# HUMI.net
KiCad netlist of a schematic drawn in Altium Designer
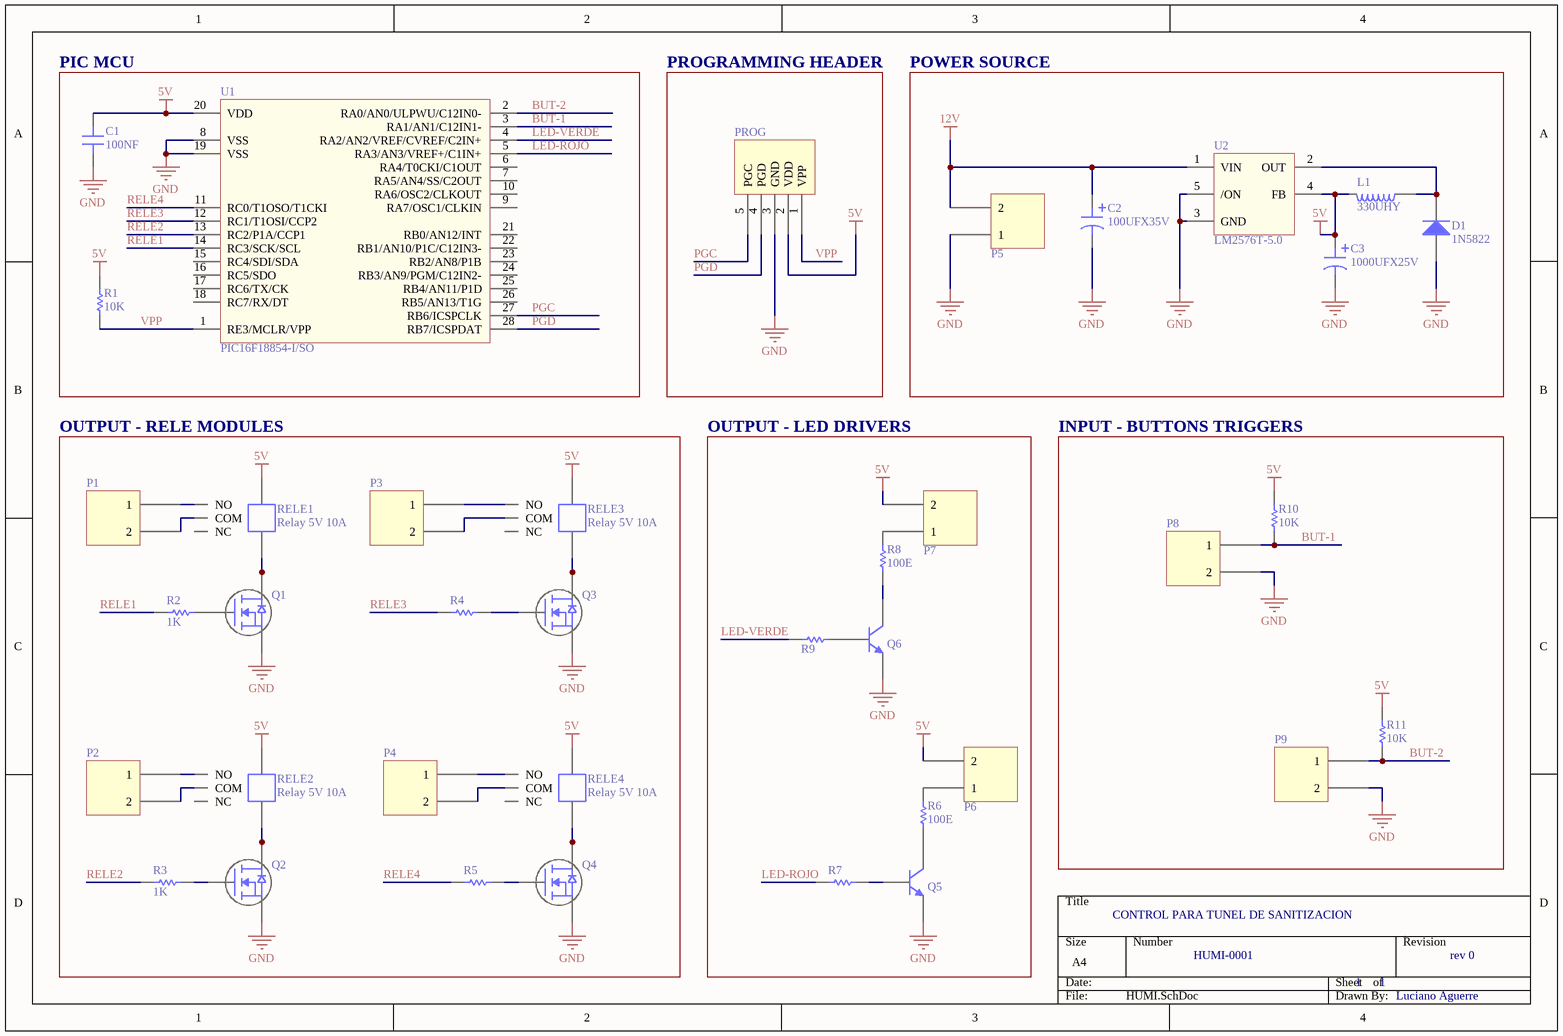
[diagram p0: HUMI.SchDoc]

(export (version "E")
  (design (tool "Eeschema 10.0.6"))
  (components
    (comp (ref "C1")
      (value "100NF")
      (footprint "CAP.SMD.0805")
      (description "100NFX50V X7R 10% CER.MULT. SMD 0805")
      (libsource (lib "Libreria-Capacitores") (part "Capacitor 100NFX50V X7R 10% CER.MULT. SMD 0805"))
    )
    (comp (ref "C2")
      (value "100UFX35V")
      (footprint "CAP-ELEC-8X11")
      (description "100UFX35V 85°C 8x11 ELE.RAD AISHI")
      (libsource (lib "Libreria-Capacitores") (part "Capacitor Electrolitico 100UFX35V 85°C 8x11 ELE.RAD AISHI"))
    )
    (comp (ref "C3")
      (value "1000UFX25V")
      (footprint "CAP-ELEC-12.5X20")
      (description "1000UFX25V 85°C 12.5X20 ELE.RAD AISHI")
      (libsource (lib "Libreria-Capacitores") (part "Capacitor Electrolitico 1000UFX25V 85°C 12.5X20 ELE.RAD AISHI"))
    )
    (comp (ref "D1")
      (value "1N5822")
      (footprint "Diode 1N5822")
      (description "Diodo Schottky 1N5822 3A 40V")
      (libsource (lib "Libreria-Diodos") (part "Diodo Schottky 1N5822 3A 40V"))
    )
    (comp (ref "L1")
      (value "330UHY")
      (footprint "Inductor Radial DR1213")
      (description "330UHY 0.3R 1.4A RAD. 15.5X15.5MM")
      (libsource (lib "Libreria-Inductores") (part "Inductor Radial 330UHY 0.3R 1.4A RAD. 15.5X15.5MM"))
    )
    (comp (ref "P1")
      (value "BORNE 2P P=5MM 1.5MM2 15A AZUL XY301V-2P")
      (footprint "CON-BOR-X2-5MM")
      (libsource (lib "Libreria-Conectores") (part "BORNE 2P P=5MM 1.5MM2 15A AZUL XY301V-2P"))
    )
    (comp (ref "P2")
      (value "BORNE 2P P=5MM 1.5MM2 15A AZUL XY301V-2P")
      (footprint "CON-BOR-X2-5MM")
      (libsource (lib "Libreria-Conectores") (part "BORNE 2P P=5MM 1.5MM2 15A AZUL XY301V-2P"))
    )
    (comp (ref "P3")
      (value "BORNE 2P P=5MM 1.5MM2 15A AZUL XY301V-2P")
      (footprint "CON-BOR-X2-5MM")
      (libsource (lib "Libreria-Conectores") (part "BORNE 2P P=5MM 1.5MM2 15A AZUL XY301V-2P"))
    )
    (comp (ref "P4")
      (value "BORNE 2P P=5MM 1.5MM2 15A AZUL XY301V-2P")
      (footprint "CON-BOR-X2-5MM")
      (libsource (lib "Libreria-Conectores") (part "BORNE 2P P=5MM 1.5MM2 15A AZUL XY301V-2P"))
    )
    (comp (ref "P5")
      (value "BORNE 2P P=5MM 1.5MM2 15A AZUL XY301V-2P")
      (footprint "CON-BOR-X2-5MM")
      (libsource (lib "") (part "BORNE 2P P=5MM 1.5MM2 15A AZUL XY301V-2P_1"))
    )
    (comp (ref "P6")
      (value "CONECTOR PWXXS MA-02 VERTICAL P=3.96MM PW02S")
      (footprint "CONECTOR PWXXS MA-02 VERTICAL P=3.96MM")
      (libsource (lib "Libreria-Conectores") (part "CONECTOR PWXXS MA-02 VERTICAL P=3.96MM PW02S"))
    )
    (comp (ref "P7")
      (value "CONECTOR PWXXS MA-02 VERTICAL P=3.96MM PW02S")
      (footprint "CONECTOR PWXXS MA-02 VERTICAL P=3.96MM")
      (libsource (lib "Libreria-Conectores") (part "CONECTOR PWXXS MA-02 VERTICAL P=3.96MM PW02S"))
    )
    (comp (ref "P8")
      (value "CONECTOR PWXXS MA-02 VERTICAL P=3.96MM PW02S")
      (footprint "CONECTOR PWXXS MA-02 VERTICAL P=3.96MM")
      (libsource (lib "") (part "CONECTOR PWXXS MA-02 VERTICAL P=3.96MM PW02S_1"))
    )
    (comp (ref "P9")
      (value "CONECTOR PWXXS MA-02 VERTICAL P=3.96MM PW02S")
      (footprint "CONECTOR PWXXS MA-02 VERTICAL P=3.96MM")
      (libsource (lib "") (part "CONECTOR PWXXS MA-02 VERTICAL P=3.96MM PW02S_1"))
    )
    (comp (ref "PROG")
      (value "In-Serial Circuit Programmer Header")
      (footprint "PIC ICSP")
      (libsource (lib "Libreria-Conectores") (part "In-Serial Circuit Programmer Header"))
    )
    (comp (ref "Q1")
      (value "Transistor MOSFET N IRFD110")
      (footprint "TRA-IRFD110")
      (libsource (lib "Libreria-Transistores") (part "Transistor MOSFET N IRFD110"))
    )
    (comp (ref "Q2")
      (value "Transistor MOSFET N IRFD110")
      (footprint "TRA-IRFD110")
      (libsource (lib "Libreria-Transistores") (part "Transistor MOSFET N IRFD110"))
    )
    (comp (ref "Q3")
      (value "Transistor MOSFET N IRFD110")
      (footprint "TRA-IRFD110")
      (libsource (lib "Libreria-Transistores") (part "Transistor MOSFET N IRFD110"))
    )
    (comp (ref "Q4")
      (value "Transistor MOSFET N IRFD110")
      (footprint "TRA-IRFD110")
      (libsource (lib "Libreria-Transistores") (part "Transistor MOSFET N IRFD110"))
    )
    (comp (ref "Q5")
      (value "BC817-40 TRA.NPN 45V0.5A 0.25W SOT23")
      (footprint "NPN.SMD.SOT23")
      (libsource (lib "Libreria-Transistores") (part "Transistor BC817-40 TRA.NPN 45V0.5A 0.25W SOT23"))
    )
    (comp (ref "Q6")
      (value "BC817-40 TRA.NPN 45V0.5A 0.25W SOT23")
      (footprint "NPN.SMD.SOT23")
      (libsource (lib "Libreria-Transistores") (part "Transistor BC817-40 TRA.NPN 45V0.5A 0.25W SOT23"))
    )
    (comp (ref "R1")
      (value "10K")
      (footprint "RES.SMD.103")
      (description "10K 5% 0805 1/8W RES.SMD")
      (libsource (lib "Libreria-Resistencias") (part "Resistencia 10K 5% 0805 1/8W"))
    )
    (comp (ref "R2")
      (value "1K")
      (footprint "RES.SMD.102")
      (description "1K 5% 0805 1/8W RES.SMD")
      (libsource (lib "Libreria-Resistencias") (part "Resistencia 1K 5% 0805 1/8W"))
    )
    (comp (ref "R3")
      (value "1K")
      (footprint "RES.SMD.102")
      (description "1K 5% 0805 1/8W RES.SMD")
      (libsource (lib "Libreria-Resistencias") (part "Resistencia 1K 5% 0805 1/8W"))
    )
    (comp (ref "R4")
      (value "1K 5% 0805 1/8W RES.SMD")
      (footprint "RES.SMD.102")
      (libsource (lib "Libreria-Resistencias") (part "Resistencia 1K 5% 0805 1/8W"))
    )
    (comp (ref "R5")
      (value "1K 5% 0805 1/8W RES.SMD")
      (footprint "RES.SMD.102")
      (libsource (lib "Libreria-Resistencias") (part "Resistencia 1K 5% 0805 1/8W"))
    )
    (comp (ref "R6")
      (value "100E")
      (footprint "RES.SMD.101")
      (description "100E 5% 0805 1/8W RES.SMD")
      (libsource (lib "Libreria-Resistencias") (part "Resistencia 100E 5% 0805 1/8W"))
    )
    (comp (ref "R7")
      (value "1K 5% 0805 1/8W RES.SMD")
      (footprint "RES.SMD.102")
      (libsource (lib "Libreria-Resistencias") (part "Resistencia 1K 5% 0805 1/8W"))
    )
    (comp (ref "R8")
      (value "100E")
      (footprint "RES.SMD.101")
      (description "100E 5% 0805 1/8W RES.SMD")
      (libsource (lib "Libreria-Resistencias") (part "Resistencia 100E 5% 0805 1/8W"))
    )
    (comp (ref "R9")
      (value "1K 5% 0805 1/8W RES.SMD")
      (footprint "RES.SMD.102")
      (libsource (lib "Libreria-Resistencias") (part "Resistencia 1K 5% 0805 1/8W"))
    )
    (comp (ref "R10")
      (value "10K")
      (footprint "RES.SMD.103")
      (description "10K 5% 0805 1/8W RES.SMD")
      (libsource (lib "Libreria-Resistencias") (part "Resistencia 10K 5% 0805 1/8W"))
    )
    (comp (ref "R11")
      (value "10K")
      (footprint "RES.SMD.103")
      (description "10K 5% 0805 1/8W RES.SMD")
      (libsource (lib "Libreria-Resistencias") (part "Resistencia 10K 5% 0805 1/8W"))
    )
    (comp (ref "RELE1")
      (value "Relay 5V 10A")
      (footprint "VAR-RELE-5V10A")
      (description "Relay simple inversor 5V 10A")
      (libsource (lib "Libreria-Varios") (part "VAR-RELE-5V Relay simple inversor 5V 10A"))
    )
    (comp (ref "RELE2")
      (value "Relay 5V 10A")
      (footprint "VAR-RELE-5V10A")
      (description "Relay simple inversor 5V 10A")
      (libsource (lib "Libreria-Varios") (part "VAR-RELE-5V Relay simple inversor 5V 10A"))
    )
    (comp (ref "RELE3")
      (value "Relay 5V 10A")
      (footprint "VAR-RELE-5V10A")
      (description "Relay simple inversor 5V 10A")
      (libsource (lib "Libreria-Varios") (part "VAR-RELE-5V Relay simple inversor 5V 10A"))
    )
    (comp (ref "RELE4")
      (value "Relay 5V 10A")
      (footprint "VAR-RELE-5V10A")
      (description "Relay simple inversor 5V 10A")
      (libsource (lib "Libreria-Varios") (part "VAR-RELE-5V Relay simple inversor 5V 10A"))
    )
    (comp (ref "U1")
      (value "PIC16F18854-I/SO")
      (footprint "SOIC-SO28")
      (libsource (lib "Libreria-Semiconductores") (part "PIC16F18854-I/SO 28 SOIC 7KB Flash, 512B RAM, 256B EE, 10b ADC2, DAC, Comp, PWM"))
    )
    (comp (ref "U2")
      (value "LM2576T-5.0")
      (footprint "LM2576T-5.0")
      (description "LM2576T-5.0 TO220 3A.STEP.DOWN.VOLT.REG.")
      (libsource (lib "Libreria-Semiconductores") (part "LM2576T-5.0 TO220 3A.STEP.DOWN.VOLT.REG."))
    )
  )
  (nets
    (net (code "1") (name "/BUT-1") (class "Default")
      (node (ref "P8") (pin "1") (pinfunction "1_1") (pintype "passive"))
      (node (ref "R10") (pin "1") (pinfunction "1_1") (pintype "passive"))
      (node (ref "U1") (pin "3") (pinfunction "RA1/AN1/C12IN1-_3") (pintype "passive"))
    )
    (net (code "2") (name "/BUT-2") (class "Default")
      (node (ref "P9") (pin "1") (pinfunction "1_1") (pintype "passive"))
      (node (ref "R11") (pin "1") (pinfunction "1_1") (pintype "passive"))
      (node (ref "U1") (pin "2") (pinfunction "RA0/AN0/ULPWU/C12IN0-_2") (pintype "passive"))
    )
    (net (code "3") (name "/LED-ROJO") (class "Default")
      (node (ref "R7") (pin "1") (pinfunction "1_1") (pintype "passive"))
      (node (ref "U1") (pin "5") (pinfunction "RA3/AN3/VREF+/C1IN+_5") (pintype "passive"))
    )
    (net (code "4") (name "/LED-VERDE") (class "Default")
      (node (ref "R9") (pin "1") (pinfunction "1_1") (pintype "passive"))
      (node (ref "U1") (pin "4") (pinfunction "RA2/AN2/VREF/CVREF/C2IN+_4") (pintype "passive"))
    )
    (net (code "5") (name "/PGC") (class "Default")
      (node (ref "PROG") (pin "5") (pinfunction "PGC_5") (pintype "passive"))
      (node (ref "U1") (pin "27") (pinfunction "RB6/ICSPCLK_27") (pintype "passive"))
    )
    (net (code "6") (name "/PGD") (class "Default")
      (node (ref "PROG") (pin "4") (pinfunction "PGD_4") (pintype "passive"))
      (node (ref "U1") (pin "28") (pinfunction "RB7/ICSPDAT_28") (pintype "passive"))
    )
    (net (code "7") (name "/RELE1") (class "Default")
      (node (ref "R2") (pin "1") (pinfunction "1_1") (pintype "passive"))
      (node (ref "U1") (pin "14") (pinfunction "RC3/SCK/SCL_14") (pintype "passive"))
    )
    (net (code "8") (name "/RELE2") (class "Default")
      (node (ref "R3") (pin "1") (pinfunction "1_1") (pintype "passive"))
      (node (ref "U1") (pin "13") (pinfunction "RC2/P1A/CCP1_13") (pintype "passive"))
    )
    (net (code "9") (name "/RELE3") (class "Default")
      (node (ref "R4") (pin "1") (pinfunction "1_1") (pintype "passive"))
      (node (ref "U1") (pin "12") (pinfunction "RC1/T1OSI/CCP2_12") (pintype "passive"))
    )
    (net (code "10") (name "/RELE4") (class "Default")
      (node (ref "R5") (pin "1") (pinfunction "1_1") (pintype "passive"))
      (node (ref "U1") (pin "11") (pinfunction "RC0/T1OSO/T1CKI_11") (pintype "passive"))
    )
    (net (code "11") (name "/VPP") (class "Default")
      (node (ref "PROG") (pin "1") (pinfunction "VPP_1") (pintype "passive"))
      (node (ref "R1") (pin "1") (pinfunction "1_1") (pintype "passive"))
      (node (ref "U1") (pin "1") (pinfunction "RE3/MCLR/VPP_1") (pintype "passive"))
    )
    (net (code "12") (name "5V") (class "Default")
      (node (ref "C1") (pin "2") (pinfunction "2_2") (pintype "passive"))
      (node (ref "C3") (pin "1") (pinfunction "1_1") (pintype "passive"))
      (node (ref "L1") (pin "1") (pinfunction "1_1") (pintype "passive"))
      (node (ref "P6") (pin "2") (pinfunction "2_2") (pintype "passive"))
      (node (ref "P7") (pin "2") (pinfunction "2_2") (pintype "passive"))
      (node (ref "PROG") (pin "2") (pinfunction "VDD_2") (pintype "passive"))
      (node (ref "R1") (pin "2") (pinfunction "2_2") (pintype "passive"))
      (node (ref "R10") (pin "2") (pinfunction "2_2") (pintype "passive"))
      (node (ref "R11") (pin "2") (pinfunction "2_2") (pintype "passive"))
      (node (ref "RELE1") (pin "2") (pinfunction "2_2") (pintype "passive"))
      (node (ref "RELE2") (pin "2") (pinfunction "2_2") (pintype "passive"))
      (node (ref "RELE3") (pin "2") (pinfunction "2_2") (pintype "passive"))
      (node (ref "RELE4") (pin "2") (pinfunction "2_2") (pintype "passive"))
      (node (ref "U1") (pin "20") (pinfunction "VDD_20") (pintype "passive"))
      (node (ref "U2") (pin "4") (pinfunction "FB_4") (pintype "passive"))
    )
    (net (code "13") (name "12V") (class "Default")
      (node (ref "C2") (pin "1") (pinfunction "1_1") (pintype "passive"))
      (node (ref "P5") (pin "2") (pinfunction "2_2") (pintype "passive"))
      (node (ref "U2") (pin "1") (pinfunction "VIN_1") (pintype "passive"))
    )
    (net (code "14") (name "GND") (class "Default")
      (node (ref "C1") (pin "1") (pinfunction "1_1") (pintype "passive"))
      (node (ref "C2") (pin "2") (pinfunction "2_2") (pintype "passive"))
      (node (ref "C3") (pin "2") (pinfunction "2_2") (pintype "passive"))
      (node (ref "D1") (pin "A") (pinfunction "A_A") (pintype "passive"))
      (node (ref "P5") (pin "1") (pinfunction "1_1") (pintype "passive"))
      (node (ref "P8") (pin "2") (pinfunction "2_2") (pintype "passive"))
      (node (ref "P9") (pin "2") (pinfunction "2_2") (pintype "passive"))
      (node (ref "PROG") (pin "3") (pinfunction "GND_3") (pintype "passive"))
      (node (ref "Q1") (pin "4") (pinfunction "4_4") (pintype "passive"))
      (node (ref "Q2") (pin "4") (pinfunction "4_4") (pintype "passive"))
      (node (ref "Q3") (pin "4") (pinfunction "4_4") (pintype "passive"))
      (node (ref "Q4") (pin "4") (pinfunction "4_4") (pintype "passive"))
      (node (ref "Q5") (pin "2") (pinfunction "E_2") (pintype "passive"))
      (node (ref "Q6") (pin "2") (pinfunction "E_2") (pintype "passive"))
      (node (ref "U1") (pin "19") (pinfunction "VSS_19") (pintype "passive"))
      (node (ref "U1") (pin "8") (pinfunction "VSS_8") (pintype "passive"))
      (node (ref "U2") (pin "3") (pinfunction "GND_3") (pintype "passive"))
      (node (ref "U2") (pin "5") (pinfunction "/ON_5") (pintype "passive"))
    )
    (net (code "15") (name "Net-(P6-Pad1)") (class "Default")
      (node (ref "P6") (pin "1") (pinfunction "1_1") (pintype "passive"))
      (node (ref "R6") (pin "2") (pinfunction "2_2") (pintype "passive"))
    )
    (net (code "16") (name "Net-(P7-Pad1)") (class "Default")
      (node (ref "P7") (pin "1") (pinfunction "1_1") (pintype "passive"))
      (node (ref "R8") (pin "2") (pinfunction "2_2") (pintype "passive"))
    )
    (net (code "17") (name "Net-(Q1-Pad1)") (class "Default")
      (node (ref "Q1") (pin "1") (pinfunction "1_1") (pintype "passive"))
      (node (ref "Q1") (pin "2") (pinfunction "2_2") (pintype "passive"))
      (node (ref "RELE1") (pin "1") (pinfunction "1_1") (pintype "passive"))
    )
    (net (code "18") (name "Net-(Q1-Pad3)") (class "Default")
      (node (ref "Q1") (pin "3") (pinfunction "3_3") (pintype "passive"))
      (node (ref "R2") (pin "2") (pinfunction "2_2") (pintype "passive"))
    )
    (net (code "19") (name "Net-(Q2-Pad1)") (class "Default")
      (node (ref "Q2") (pin "1") (pinfunction "1_1") (pintype "passive"))
      (node (ref "Q2") (pin "2") (pinfunction "2_2") (pintype "passive"))
      (node (ref "RELE2") (pin "1") (pinfunction "1_1") (pintype "passive"))
    )
    (net (code "20") (name "Net-(Q2-Pad3)") (class "Default")
      (node (ref "Q2") (pin "3") (pinfunction "3_3") (pintype "passive"))
      (node (ref "R3") (pin "2") (pinfunction "2_2") (pintype "passive"))
    )
    (net (code "21") (name "Net-(Q3-Pad1)") (class "Default")
      (node (ref "Q3") (pin "1") (pinfunction "1_1") (pintype "passive"))
      (node (ref "Q3") (pin "2") (pinfunction "2_2") (pintype "passive"))
      (node (ref "RELE3") (pin "1") (pinfunction "1_1") (pintype "passive"))
    )
    (net (code "22") (name "Net-(Q3-Pad3)") (class "Default")
      (node (ref "Q3") (pin "3") (pinfunction "3_3") (pintype "passive"))
      (node (ref "R4") (pin "2") (pinfunction "2_2") (pintype "passive"))
    )
    (net (code "23") (name "Net-(Q4-Pad1)") (class "Default")
      (node (ref "Q4") (pin "1") (pinfunction "1_1") (pintype "passive"))
      (node (ref "Q4") (pin "2") (pinfunction "2_2") (pintype "passive"))
      (node (ref "RELE4") (pin "1") (pinfunction "1_1") (pintype "passive"))
    )
    (net (code "24") (name "Net-(Q4-Pad3)") (class "Default")
      (node (ref "Q4") (pin "3") (pinfunction "3_3") (pintype "passive"))
      (node (ref "R5") (pin "2") (pinfunction "2_2") (pintype "passive"))
    )
    (net (code "25") (name "Net-(Q5-B)") (class "Default")
      (node (ref "Q5") (pin "1") (pinfunction "B_1") (pintype "passive"))
      (node (ref "R7") (pin "2") (pinfunction "2_2") (pintype "passive"))
    )
    (net (code "26") (name "Net-(Q5-C)") (class "Default")
      (node (ref "Q5") (pin "3") (pinfunction "C_3") (pintype "passive"))
      (node (ref "R6") (pin "1") (pinfunction "1_1") (pintype "passive"))
    )
    (net (code "27") (name "Net-(Q6-B)") (class "Default")
      (node (ref "Q6") (pin "1") (pinfunction "B_1") (pintype "passive"))
      (node (ref "R9") (pin "2") (pinfunction "2_2") (pintype "passive"))
    )
    (net (code "28") (name "Net-(Q6-C)") (class "Default")
      (node (ref "Q6") (pin "3") (pinfunction "C_3") (pintype "passive"))
      (node (ref "R8") (pin "1") (pinfunction "1_1") (pintype "passive"))
    )
    (net (code "29") (name "Net-(RELE1-COM)") (class "Default")
      (node (ref "P1") (pin "2") (pinfunction "2_2") (pintype "passive"))
      (node (ref "RELE1") (pin "3") (pinfunction "COM_3") (pintype "passive"))
    )
    (net (code "30") (name "Net-(RELE1-NO)") (class "Default")
      (node (ref "P1") (pin "1") (pinfunction "1_1") (pintype "passive"))
      (node (ref "RELE1") (pin "4") (pinfunction "NO_4") (pintype "passive"))
    )
    (net (code "31") (name "Net-(RELE2-COM)") (class "Default")
      (node (ref "P2") (pin "2") (pinfunction "2_2") (pintype "passive"))
      (node (ref "RELE2") (pin "3") (pinfunction "COM_3") (pintype "passive"))
    )
    (net (code "32") (name "Net-(RELE2-NO)") (class "Default")
      (node (ref "P2") (pin "1") (pinfunction "1_1") (pintype "passive"))
      (node (ref "RELE2") (pin "4") (pinfunction "NO_4") (pintype "passive"))
    )
    (net (code "33") (name "Net-(RELE3-COM)") (class "Default")
      (node (ref "P3") (pin "2") (pinfunction "2_2") (pintype "passive"))
      (node (ref "RELE3") (pin "3") (pinfunction "COM_3") (pintype "passive"))
    )
    (net (code "34") (name "Net-(RELE3-NO)") (class "Default")
      (node (ref "P3") (pin "1") (pinfunction "1_1") (pintype "passive"))
      (node (ref "RELE3") (pin "4") (pinfunction "NO_4") (pintype "passive"))
    )
    (net (code "35") (name "Net-(RELE4-COM)") (class "Default")
      (node (ref "P4") (pin "2") (pinfunction "2_2") (pintype "passive"))
      (node (ref "RELE4") (pin "3") (pinfunction "COM_3") (pintype "passive"))
    )
    (net (code "36") (name "Net-(RELE4-NO)") (class "Default")
      (node (ref "P4") (pin "1") (pinfunction "1_1") (pintype "passive"))
      (node (ref "RELE4") (pin "4") (pinfunction "NO_4") (pintype "passive"))
    )
    (net (code "37") (name "Net-(U2-OUT)") (class "Default")
      (node (ref "D1") (pin "K") (pinfunction "K_K") (pintype "passive"))
      (node (ref "L1") (pin "2") (pinfunction "2_2") (pintype "passive"))
      (node (ref "U2") (pin "2") (pinfunction "OUT_2") (pintype "passive"))
    )
    (net (code "38") (name "unconnected-(RELE1-NC-Pad5)") (class "Default")
      (node (ref "RELE1") (pin "5") (pinfunction "NC_5") (pintype "passive"))
    )
    (net (code "39") (name "unconnected-(RELE2-NC-Pad5)") (class "Default")
      (node (ref "RELE2") (pin "5") (pinfunction "NC_5") (pintype "passive"))
    )
    (net (code "40") (name "unconnected-(RELE3-NC-Pad5)") (class "Default")
      (node (ref "RELE3") (pin "5") (pinfunction "NC_5") (pintype "passive"))
    )
    (net (code "41") (name "unconnected-(RELE4-NC-Pad5)") (class "Default")
      (node (ref "RELE4") (pin "5") (pinfunction "NC_5") (pintype "passive"))
    )
    (net (code "42") (name "unconnected-(U1-RA4{slash}T0CKI{slash}C1OUT-Pad6)") (class "Default")
      (node (ref "U1") (pin "6") (pinfunction "RA4/T0CKI/C1OUT_6") (pintype "passive"))
    )
    (net (code "43") (name "unconnected-(U1-RA5{slash}AN4{slash}SS{slash}C2OUT-Pad7)") (class "Default")
      (node (ref "U1") (pin "7") (pinfunction "RA5/AN4/SS/C2OUT_7") (pintype "passive"))
    )
    (net (code "44") (name "unconnected-(U1-RA6{slash}OSC2{slash}CLKOUT-Pad10)") (class "Default")
      (node (ref "U1") (pin "10") (pinfunction "RA6/OSC2/CLKOUT_10") (pintype "passive"))
    )
    (net (code "45") (name "unconnected-(U1-RA7{slash}OSC1{slash}CLKIN-Pad9)") (class "Default")
      (node (ref "U1") (pin "9") (pinfunction "RA7/OSC1/CLKIN_9") (pintype "passive"))
    )
    (net (code "46") (name "unconnected-(U1-RB0{slash}AN12{slash}INT-Pad21)") (class "Default")
      (node (ref "U1") (pin "21") (pinfunction "RB0/AN12/INT_21") (pintype "passive"))
    )
    (net (code "47") (name "unconnected-(U1-RB1{slash}AN10{slash}P1C{slash}C12IN3--Pad22)") (class "Default")
      (node (ref "U1") (pin "22") (pinfunction "RB1/AN10/P1C/C12IN3-_22") (pintype "passive"))
    )
    (net (code "48") (name "unconnected-(U1-RB2{slash}AN8{slash}P1B-Pad23)") (class "Default")
      (node (ref "U1") (pin "23") (pinfunction "RB2/AN8/P1B_23") (pintype "passive"))
    )
    (net (code "49") (name "unconnected-(U1-RB3{slash}AN9{slash}PGM{slash}C12IN2--Pad24)") (class "Default")
      (node (ref "U1") (pin "24") (pinfunction "RB3/AN9/PGM/C12IN2-_24") (pintype "passive"))
    )
    (net (code "50") (name "unconnected-(U1-RB4{slash}AN11{slash}P1D-Pad25)") (class "Default")
      (node (ref "U1") (pin "25") (pinfunction "RB4/AN11/P1D_25") (pintype "passive"))
    )
    (net (code "51") (name "unconnected-(U1-RB5{slash}AN13{slash}T1G-Pad26)") (class "Default")
      (node (ref "U1") (pin "26") (pinfunction "RB5/AN13/T1G_26") (pintype "passive"))
    )
    (net (code "52") (name "unconnected-(U1-RC4{slash}SDI{slash}SDA-Pad15)") (class "Default")
      (node (ref "U1") (pin "15") (pinfunction "RC4/SDI/SDA_15") (pintype "passive"))
    )
    (net (code "53") (name "unconnected-(U1-RC5{slash}SDO-Pad16)") (class "Default")
      (node (ref "U1") (pin "16") (pinfunction "RC5/SDO_16") (pintype "passive"))
    )
    (net (code "54") (name "unconnected-(U1-RC6{slash}TX{slash}CK-Pad17)") (class "Default")
      (node (ref "U1") (pin "17") (pinfunction "RC6/TX/CK_17") (pintype "passive"))
    )
    (net (code "55") (name "unconnected-(U1-RC7{slash}RX{slash}DT-Pad18)") (class "Default")
      (node (ref "U1") (pin "18") (pinfunction "RC7/RX/DT_18") (pintype "passive"))
    )
  )
)
